# PLACALDR.net
KiCad netlist of a schematic drawn in Altium Designer
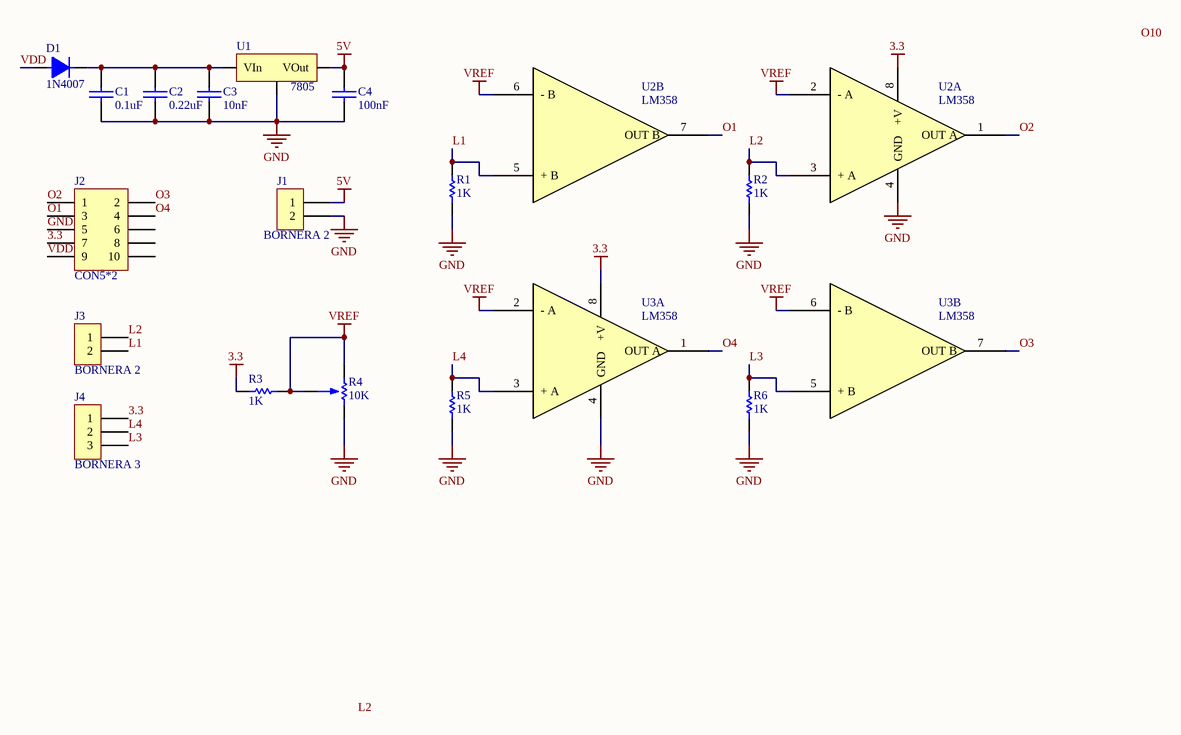
[diagram p0: PLACALDR.SchDoc]

(export (version "E")
  (design (tool "Eeschema 10.0.6"))
  (components
    (comp (ref "C1") (value "0.1uF") (footprint "CAP100") (libsource (lib "LIBEBAL") (part "CAP")))
    (comp (ref "C2") (value "0.22uF") (footprint "CAP100") (libsource (lib "LIBEBAL") (part "CAP")))
    (comp (ref "C3") (value "10nF") (footprint "CAP100") (libsource (lib "LIBEBAL") (part "CAP")))
    (comp (ref "C4") (value "100nF") (footprint "CAP100") (libsource (lib "LIBEBAL") (part "CAP")))
    (comp (ref "D1") (value "1N4007") (footprint "DO41") (libsource (lib "LIBEBAL") (part "DIODO")))
    (comp (ref "J1")
      (value "BORNERA 2")
      (footprint "BORNERA2")
      (libsource (lib "LIBEBAL") (part "BORNERA 2"))
    )
    (comp (ref "J2") (value "CON5*2") (footprint "SIP5*2") (libsource (lib "LIBEBAL") (part "CON5*2")))
    (comp (ref "J3")
      (value "BORNERA 2")
      (footprint "BORNERA2")
      (libsource (lib "LIBEBAL") (part "BORNERA 2"))
    )
    (comp (ref "J4")
      (value "BORNERA 3")
      (footprint "BORNERA3")
      (libsource (lib "LIBEBAL") (part "BORNERA 3"))
    )
    (comp (ref "R1") (value "1K") (footprint "RES400") (libsource (lib "LibGorra") (part "RES")))
    (comp (ref "R2") (value "1K") (footprint "RES400") (libsource (lib "LibGorra") (part "RES")))
    (comp (ref "R3") (value "1K") (footprint "RES400") (libsource (lib "LibGorra") (part "RES")))
    (comp (ref "R4") (value "10K") (footprint "PRESET H") (libsource (lib "LibGorra") (part "PRESET")))
    (comp (ref "R5") (value "1K") (footprint "RES400") (libsource (lib "LibGorra") (part "RES")))
    (comp (ref "R6") (value "1K") (footprint "RES400") (libsource (lib "LibGorra") (part "RES")))
    (comp (ref "U1")
      (value "7805")
      (footprint "TO-220 V")
      (description "REGULDOR POSITIVO")
      (libsource (lib "LIBEBAL") (part "78XX"))
    )
    (comp (ref "U2") (value "LM358") (footprint "DIP8") (libsource (lib "LibGorra") (part "LM358")))
    (comp (ref "U3") (value "LM358") (footprint "DIP8") (libsource (lib "LibGorra") (part "LM358")))
  )
  (nets
    (net (code "1") (name "/L1") (class "Default")
      (node (ref "J3") (pin "2") (pinfunction "2_2") (pintype "passive"))
      (node (ref "R1") (pin "1") (pinfunction "1_1") (pintype "passive"))
      (node (ref "U2") (pin "5") (pinfunction "+_B_5") (pintype "passive"))
    )
    (net (code "2") (name "/L2") (class "Default")
      (node (ref "J3") (pin "1") (pinfunction "1_1") (pintype "passive"))
      (node (ref "R2") (pin "1") (pinfunction "1_1") (pintype "passive"))
      (node (ref "U2") (pin "3") (pinfunction "+_A_3") (pintype "passive"))
    )
    (net (code "3") (name "/L3") (class "Default")
      (node (ref "J4") (pin "3") (pinfunction "3_3") (pintype "passive"))
      (node (ref "R6") (pin "1") (pinfunction "1_1") (pintype "passive"))
      (node (ref "U3") (pin "5") (pinfunction "+_B_5") (pintype "passive"))
    )
    (net (code "4") (name "/L4") (class "Default")
      (node (ref "J4") (pin "2") (pinfunction "2_2") (pintype "passive"))
      (node (ref "R5") (pin "1") (pinfunction "1_1") (pintype "passive"))
      (node (ref "U3") (pin "3") (pinfunction "+_A_3") (pintype "passive"))
    )
    (net (code "5") (name "/O1") (class "Default")
      (node (ref "J2") (pin "3") (pinfunction "3_3") (pintype "passive"))
      (node (ref "U2") (pin "7") (pinfunction "OUT_B_7") (pintype "passive"))
    )
    (net (code "6") (name "/O2") (class "Default")
      (node (ref "J2") (pin "1") (pinfunction "1_1") (pintype "passive"))
      (node (ref "U2") (pin "1") (pinfunction "OUT_A_1") (pintype "passive"))
    )
    (net (code "7") (name "/O3") (class "Default")
      (node (ref "J2") (pin "2") (pinfunction "2_2") (pintype "passive"))
      (node (ref "U3") (pin "7") (pinfunction "OUT_B_7") (pintype "passive"))
    )
    (net (code "8") (name "/O4") (class "Default")
      (node (ref "J2") (pin "4") (pinfunction "4_4") (pintype "passive"))
      (node (ref "U3") (pin "1") (pinfunction "OUT_A_1") (pintype "passive"))
    )
    (net (code "10") (name "/VDD") (class "Default")
      (node (ref "D1") (pin "1") (pinfunction "1_1") (pintype "passive"))
      (node (ref "J2") (pin "9") (pinfunction "9_9") (pintype "passive"))
    )
    (net (code "11") (name "3.3") (class "Default")
      (node (ref "J2") (pin "7") (pinfunction "7_7") (pintype "passive"))
      (node (ref "J4") (pin "1") (pinfunction "1_1") (pintype "passive"))
      (node (ref "R3") (pin "2") (pinfunction "2_2") (pintype "passive"))
      (node (ref "U2") (pin "8") (pinfunction "+V_8") (pintype "passive"))
      (node (ref "U3") (pin "8") (pinfunction "+V_8") (pintype "passive"))
    )
    (net (code "12") (name "5V") (class "Default")
      (node (ref "C4") (pin "1") (pinfunction "1_1") (pintype "passive"))
      (node (ref "J1") (pin "1") (pinfunction "1_1") (pintype "passive"))
      (node (ref "U1") (pin "3") (pinfunction "VOut_3") (pintype "passive"))
    )
    (net (code "13") (name "GND") (class "Default")
      (node (ref "C1") (pin "2") (pinfunction "2_2") (pintype "passive"))
      (node (ref "C2") (pin "2") (pinfunction "2_2") (pintype "passive"))
      (node (ref "C3") (pin "2") (pinfunction "2_2") (pintype "passive"))
      (node (ref "C4") (pin "2") (pinfunction "2_2") (pintype "passive"))
      (node (ref "J1") (pin "2") (pinfunction "2_2") (pintype "passive"))
      (node (ref "J2") (pin "5") (pinfunction "5_5") (pintype "passive"))
      (node (ref "R1") (pin "2") (pinfunction "2_2") (pintype "passive"))
      (node (ref "R2") (pin "2") (pinfunction "2_2") (pintype "passive"))
      (node (ref "R4") (pin "1") (pinfunction "1_1") (pintype "passive"))
      (node (ref "R5") (pin "2") (pinfunction "2_2") (pintype "passive"))
      (node (ref "R6") (pin "2") (pinfunction "2_2") (pintype "passive"))
      (node (ref "U1") (pin "2") (pinfunction "GND_2") (pintype "passive"))
      (node (ref "U2") (pin "4") (pinfunction "GND_4") (pintype "passive"))
      (node (ref "U3") (pin "4") (pinfunction "GND_4") (pintype "passive"))
    )
    (net (code "14") (name "Net-(U1-VIn)") (class "Default")
      (node (ref "C1") (pin "1") (pinfunction "1_1") (pintype "passive"))
      (node (ref "C2") (pin "1") (pinfunction "1_1") (pintype "passive"))
      (node (ref "C3") (pin "1") (pinfunction "1_1") (pintype "passive"))
      (node (ref "D1") (pin "2") (pinfunction "2_2") (pintype "passive"))
      (node (ref "U1") (pin "1") (pinfunction "VIn_1") (pintype "passive"))
    )
    (net (code "15") (name "VREF") (class "Default")
      (node (ref "R3") (pin "1") (pinfunction "1_1") (pintype "passive"))
      (node (ref "R4") (pin "2") (pinfunction "2_2") (pintype "passive"))
      (node (ref "R4") (pin "3") (pinfunction "3_3") (pintype "passive"))
      (node (ref "U2") (pin "2") (pinfunction "-_A_2") (pintype "passive"))
      (node (ref "U2") (pin "6") (pinfunction "-_B_6") (pintype "passive"))
      (node (ref "U3") (pin "2") (pinfunction "-_A_2") (pintype "passive"))
      (node (ref "U3") (pin "6") (pinfunction "-_B_6") (pintype "passive"))
    )
    (net (code "16") (name "unconnected-(J2-Pad6)") (class "Default")
      (node (ref "J2") (pin "6") (pinfunction "6_6") (pintype "passive"))
    )
    (net (code "17") (name "unconnected-(J2-Pad8)") (class "Default")
      (node (ref "J2") (pin "8") (pinfunction "8_8") (pintype "passive"))
    )
    (net (code "18") (name "unconnected-(J2-Pad10)") (class "Default")
      (node (ref "J2") (pin "10") (pinfunction "10_10") (pintype "passive"))
    )
  )
)
